# Acceleration.net
KiCad netlist of a schematic drawn in Altium Designer
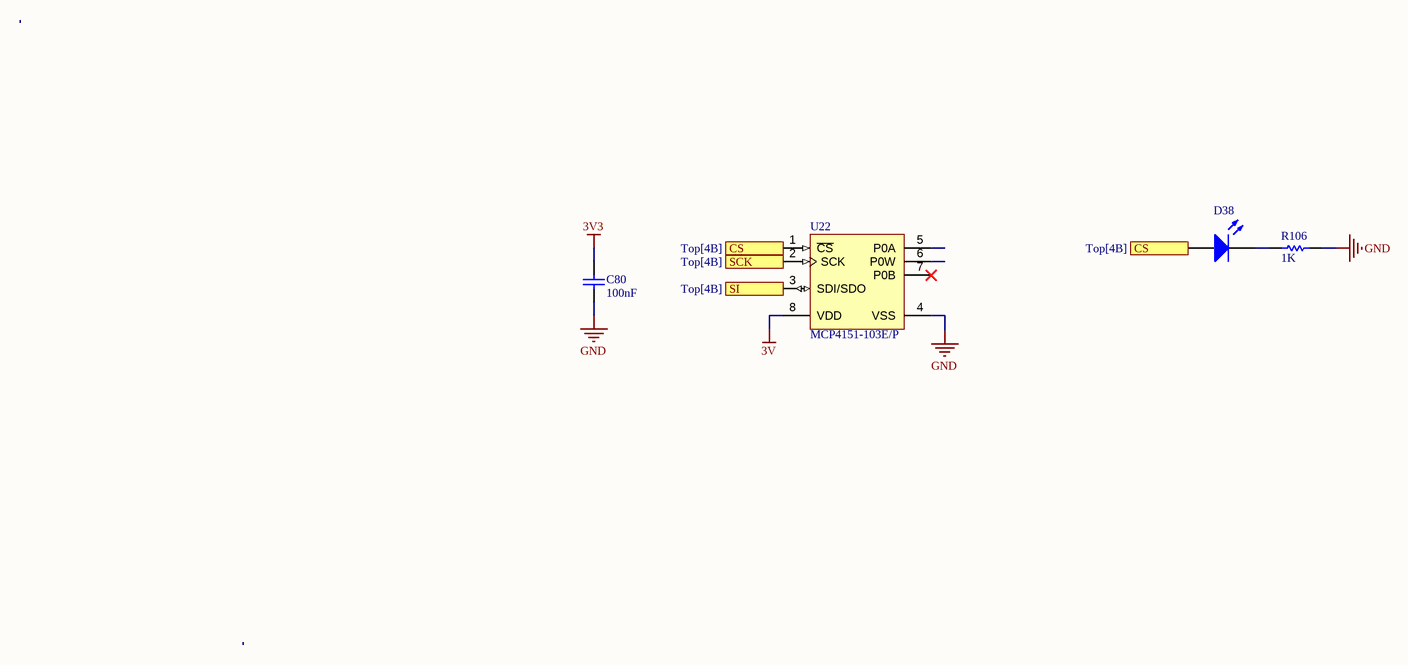
[diagram p0: Acceleration.SchDoc]

(export (version "E")
  (design (tool "Eeschema 10.0.6"))
  (components
    (comp (ref "C80")
      (value "100nF")
      (description "Capacitor")
      (libsource (lib "Simulation Generic Components") (part "Capacitor"))
    )
    (comp (ref "D38")
      (value "Light-Emitting Diode")
      (libsource (lib "Simulation Generic Components") (part "LED"))
    )
    (comp (ref "R106")
      (value "1K")
      (description "Resistor")
      (libsource (lib "Simulation Generic Components") (part "Resistor"))
    )
    (comp (ref "U22")
      (value "MCP4151-103E/P")
      (footprint "PDIP300-P8")
      (description "7/8-Bit Single/Dual SPI Digital POT with Volatile Memory, 8-Pin PDIP, Extended Temperature")
      (libsource (lib "Altium Content Vault") (part "IN-DPOT-MCP41X1-8"))
    )
  )
  (nets
    (net (code "1") (name "/CS") (class "Default")
      (node (ref "D38") (pin "1") (pinfunction "A_1") (pintype "passive"))
      (node (ref "U22") (pin "1") (pinfunction "~{CS}_1") (pintype "input"))
    )
    (net (code "2") (name "/SCK") (class "Default")
      (node (ref "U22") (pin "2") (pinfunction "SCK_2") (pintype "input"))
    )
    (net (code "3") (name "/SI") (class "Default")
      (node (ref "U22") (pin "3") (pinfunction "SDI/SDO_3") (pintype "bidirectional"))
    )
    (net (code "4") (name "3V") (class "Default")
      (node (ref "U22") (pin "8") (pinfunction "VDD_8") (pintype "power_in"))
    )
    (net (code "5") (name "3V3") (class "Default")
      (node (ref "C80") (pin "2") (pinfunction "2_2") (pintype "passive"))
    )
    (net (code "6") (name "GND") (class "Default")
      (node (ref "C80") (pin "1") (pinfunction "1_1") (pintype "passive"))
      (node (ref "R106") (pin "2") (pinfunction "2_2") (pintype "passive"))
      (node (ref "U22") (pin "4") (pinfunction "VSS_4") (pintype "power_in"))
    )
    (net (code "7") (name "Net-(D38-K)") (class "Default")
      (node (ref "D38") (pin "2") (pinfunction "K_2") (pintype "passive"))
      (node (ref "R106") (pin "1") (pinfunction "1_1") (pintype "passive"))
    )
    (net (code "8") (name "unconnected-(U22-P0A-Pad5)") (class "Default")
      (node (ref "U22") (pin "5") (pinfunction "P0A_5") (pintype "passive"))
    )
    (net (code "9") (name "unconnected-(U22-P0B-Pad7)") (class "Default")
      (node (ref "U22") (pin "7") (pinfunction "P0B_7") (pintype "passive+no_connect"))
    )
    (net (code "10") (name "unconnected-(U22-P0W-Pad6)") (class "Default")
      (node (ref "U22") (pin "6") (pinfunction "P0W_6") (pintype "passive"))
    )
  )
)
